# 11_SCREEN.net
KiCad netlist of a schematic drawn in Altium Designer
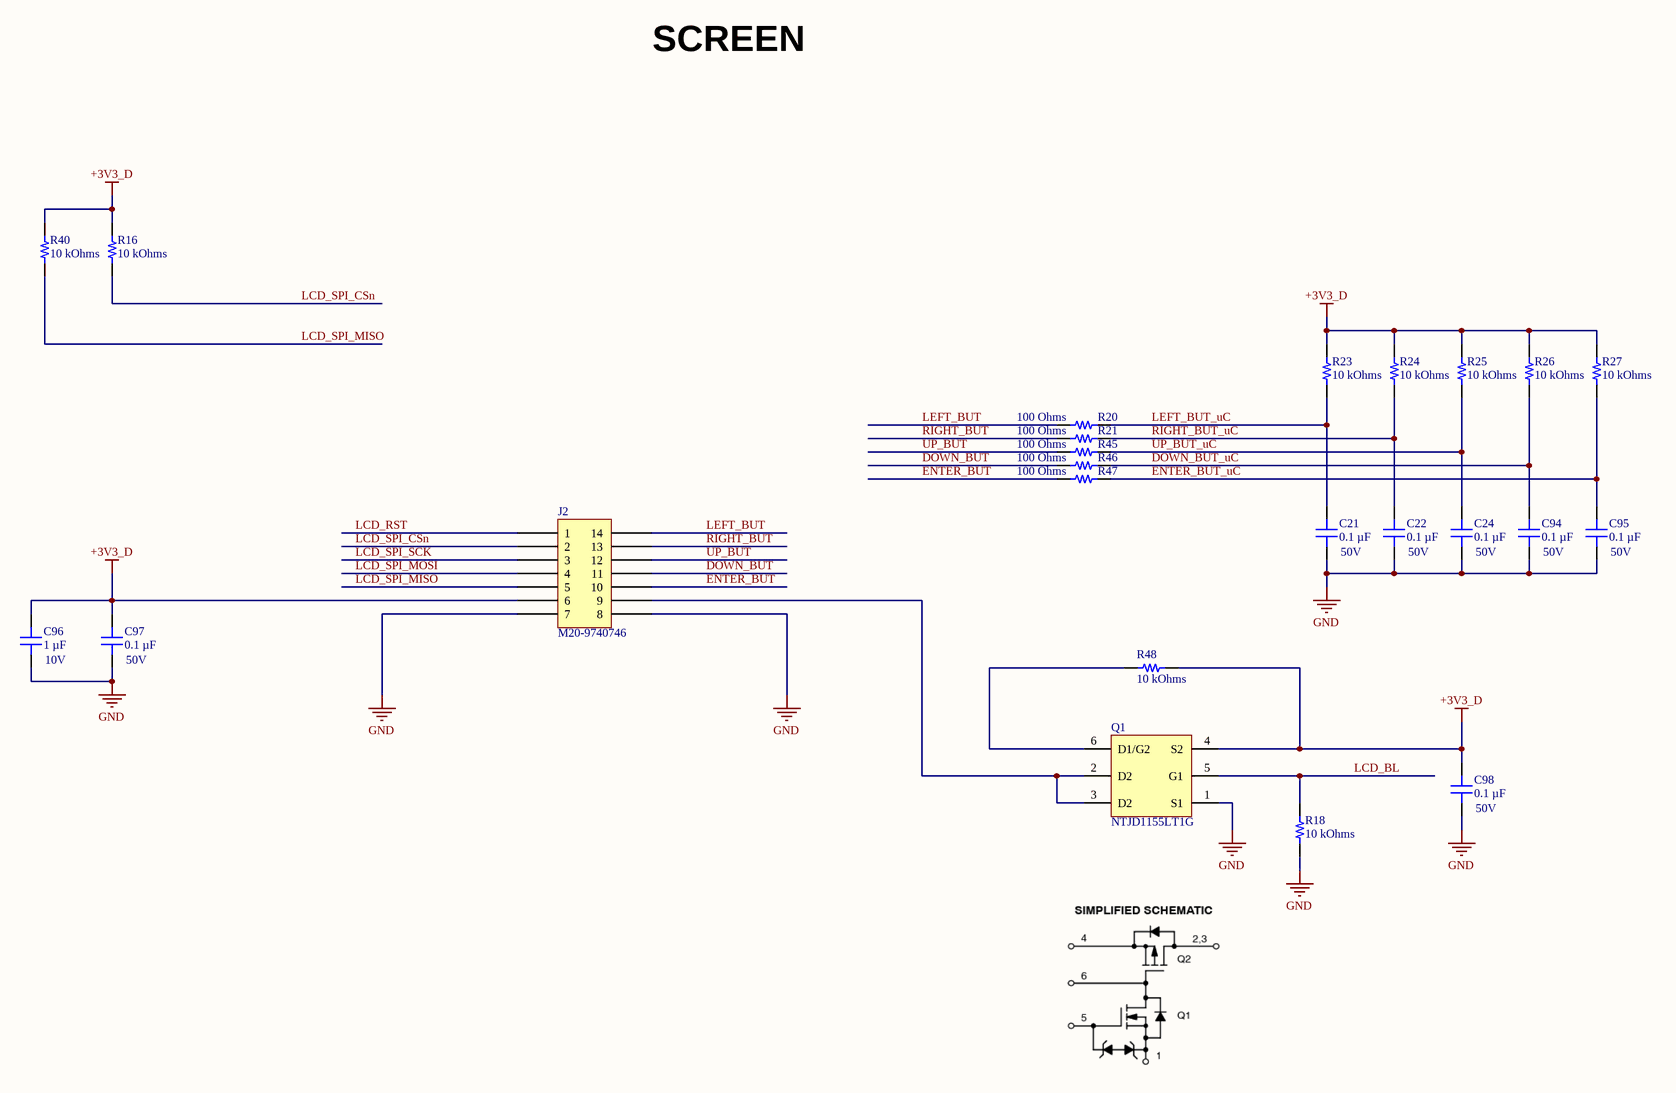
[diagram p0: 11_SCREEN.SchDoc]

(export (version "E")
  (design (tool "Eeschema 10.0.6"))
  (components
    (comp (ref "C21")
      (value "0.1 µF")
      (footprint "CAP 0402_1005")
      (description "CAP CER 0.1UF 50V X7R 0402")
      (fields
        (field (name "PART NUMBER") "GCM155R71H104KE02J")
        (field (name "CAPACITANCE") "0.1 µF")
        (field (name "MANUFACTURER") "Murata Electronics")
        (field (name "VOLTAGE - RATED") "50V")
      )
      (libsource (lib "Celestial Altium Library - altium_library") (part "Capacitor"))
    )
    (comp (ref "C22")
      (value "0.1 µF")
      (footprint "CAP 0402_1005")
      (description "CAP CER 0.1UF 50V X7R 0402")
      (fields
        (field (name "PART NUMBER") "GCM155R71H104KE02J")
        (field (name "CAPACITANCE") "0.1 µF")
        (field (name "MANUFACTURER") "Murata Electronics")
        (field (name "VOLTAGE - RATED") "50V")
      )
      (libsource (lib "Celestial Altium Library - altium_library") (part "Capacitor"))
    )
    (comp (ref "C24")
      (value "0.1 µF")
      (footprint "CAP 0402_1005")
      (description "CAP CER 0.1UF 50V X7R 0402")
      (fields
        (field (name "PART NUMBER") "GCM155R71H104KE02J")
        (field (name "CAPACITANCE") "0.1 µF")
        (field (name "MANUFACTURER") "Murata Electronics")
        (field (name "VOLTAGE - RATED") "50V")
      )
      (libsource (lib "Celestial Altium Library - altium_library") (part "Capacitor"))
    )
    (comp (ref "C94")
      (value "0.1 µF")
      (footprint "CAP 0402_1005")
      (description "CAP CER 0.1UF 50V X7R 0402")
      (fields
        (field (name "PART NUMBER") "GCM155R71H104KE02J")
        (field (name "CAPACITANCE") "0.1 µF")
        (field (name "MANUFACTURER") "Murata Electronics")
        (field (name "VOLTAGE - RATED") "50V")
      )
      (libsource (lib "Celestial Altium Library - altium_library") (part "Capacitor"))
    )
    (comp (ref "C95")
      (value "0.1 µF")
      (footprint "CAP 0402_1005")
      (description "CAP CER 0.1UF 50V X7R 0402")
      (fields
        (field (name "PART NUMBER") "GCM155R71H104KE02J")
        (field (name "CAPACITANCE") "0.1 µF")
        (field (name "MANUFACTURER") "Murata Electronics")
        (field (name "VOLTAGE - RATED") "50V")
      )
      (libsource (lib "Celestial Altium Library - altium_library") (part "Capacitor"))
    )
    (comp (ref "C96")
      (value "1 µF")
      (footprint "CAP 0402_1005")
      (description "CAP CER 1UF 10V X7S 0402")
      (fields
        (field (name "PART NUMBER") "GRM155C71A105KE11D")
        (field (name "CAPACITANCE") "1 µF")
        (field (name "MANUFACTURER") "Murata Electronics")
        (field (name "VOLTAGE - RATED") "10V")
      )
      (libsource (lib "Celestial Altium Library - altium_library") (part "Capacitor"))
    )
    (comp (ref "C97")
      (value "0.1 µF")
      (footprint "CAP 0402_1005")
      (description "CAP CER 0.1UF 50V X7R 0402")
      (fields
        (field (name "PART NUMBER") "GCM155R71H104KE02J")
        (field (name "CAPACITANCE") "0.1 µF")
        (field (name "MANUFACTURER") "Murata Electronics")
        (field (name "VOLTAGE - RATED") "50V")
      )
      (libsource (lib "Celestial Altium Library - altium_library") (part "Capacitor"))
    )
    (comp (ref "C98")
      (value "0.1 µF")
      (footprint "CAP 0402_1005")
      (description "CAP CER 0.1UF 50V X7R 0402")
      (fields
        (field (name "PART NUMBER") "GCM155R71H104KE02J")
        (field (name "CAPACITANCE") "0.1 µF")
        (field (name "MANUFACTURER") "Murata Electronics")
        (field (name "VOLTAGE - RATED") "50V")
      )
      (libsource (lib "Celestial Altium Library - altium_library") (part "Capacitor"))
    )
    (comp (ref "J2")
      (value "M20-9740746")
      (footprint "HARWIN M20-9740745")
      (description "CONN HEADER R/A 14POS 2.54MM")
      (fields (field (name "MANUFACTURER") "Harwin Inc."))
      (libsource (lib "Celestial Altium Library - altium_library") (part "2X7 PIN DU"))
    )
    (comp (ref "Q1")
      (value "NTJD1155LT1G")
      (footprint "ONSC-SC70-6-419B-02_W_V")
      (fields (field (name "MANUFACTURER") "On Semiconductor"))
      (libsource (lib "Altium Content Vault") (part "ONSC-PNMOS-6_D"))
    )
    (comp (ref "R16")
      (value "10 kOhms")
      (footprint "RES 0402_1005")
      (description "RES 10K OHM 1% 1/16W 0402")
      (fields (field (name "PART NUMBER") "RC0402FR-0710KL") (field (name "MANUFACTURER") "Yageo"))
      (libsource (lib "Celestial Altium Library - altium_library") (part "Resistor"))
    )
    (comp (ref "R18")
      (value "10 kOhms")
      (footprint "RES 0402_1005")
      (description "RES 10K OHM 1% 1/16W 0402")
      (fields (field (name "PART NUMBER") "RC0402FR-0710KL") (field (name "MANUFACTURER") "Yageo"))
      (libsource (lib "Celestial Altium Library - altium_library") (part "Resistor"))
    )
    (comp (ref "R20")
      (value "100 Ohms")
      (footprint "RES 0402_1005")
      (description "RES SMD 100 OHM 1% 1/16W 0402")
      (fields (field (name "PART NUMBER") "RT0402FRE07100RL") (field (name "MANUFACTURER") "Yageo"))
      (libsource (lib "Celestial Altium Library - altium_library") (part "Resistor"))
    )
    (comp (ref "R21")
      (value "100 Ohms")
      (footprint "RES 0402_1005")
      (description "RES SMD 100 OHM 1% 1/16W 0402")
      (fields (field (name "PART NUMBER") "RT0402FRE07100RL") (field (name "MANUFACTURER") "Yageo"))
      (libsource (lib "Celestial Altium Library - altium_library") (part "Resistor"))
    )
    (comp (ref "R23")
      (value "10 kOhms")
      (footprint "RES 0402_1005")
      (description "RES 10K OHM 1% 1/16W 0402")
      (fields (field (name "PART NUMBER") "RC0402FR-0710KL") (field (name "MANUFACTURER") "Yageo"))
      (libsource (lib "Celestial Altium Library - altium_library") (part "Resistor"))
    )
    (comp (ref "R24")
      (value "10 kOhms")
      (footprint "RES 0402_1005")
      (description "RES 10K OHM 1% 1/16W 0402")
      (fields (field (name "PART NUMBER") "RC0402FR-0710KL") (field (name "MANUFACTURER") "Yageo"))
      (libsource (lib "Celestial Altium Library - altium_library") (part "Resistor"))
    )
    (comp (ref "R25")
      (value "10 kOhms")
      (footprint "RES 0402_1005")
      (description "RES 10K OHM 1% 1/16W 0402")
      (fields (field (name "PART NUMBER") "RC0402FR-0710KL") (field (name "MANUFACTURER") "Yageo"))
      (libsource (lib "Celestial Altium Library - altium_library") (part "Resistor"))
    )
    (comp (ref "R26")
      (value "10 kOhms")
      (footprint "RES 0402_1005")
      (description "RES 10K OHM 1% 1/16W 0402")
      (fields (field (name "PART NUMBER") "RC0402FR-0710KL") (field (name "MANUFACTURER") "Yageo"))
      (libsource (lib "Celestial Altium Library - altium_library") (part "Resistor"))
    )
    (comp (ref "R27")
      (value "10 kOhms")
      (footprint "RES 0402_1005")
      (description "RES 10K OHM 1% 1/16W 0402")
      (fields (field (name "PART NUMBER") "RC0402FR-0710KL") (field (name "MANUFACTURER") "Yageo"))
      (libsource (lib "Celestial Altium Library - altium_library") (part "Resistor"))
    )
    (comp (ref "R40")
      (value "10 kOhms")
      (footprint "RES 0402_1005")
      (description "RES 10K OHM 1% 1/16W 0402")
      (fields (field (name "PART NUMBER") "RC0402FR-0710KL") (field (name "MANUFACTURER") "Yageo"))
      (libsource (lib "Celestial Altium Library - altium_library") (part "Resistor"))
    )
    (comp (ref "R45")
      (value "100 Ohms")
      (footprint "RES 0402_1005")
      (description "RES SMD 100 OHM 1% 1/16W 0402")
      (fields (field (name "PART NUMBER") "RT0402FRE07100RL") (field (name "MANUFACTURER") "Yageo"))
      (libsource (lib "Celestial Altium Library - altium_library") (part "Resistor"))
    )
    (comp (ref "R46")
      (value "100 Ohms")
      (footprint "RES 0402_1005")
      (description "RES SMD 100 OHM 1% 1/16W 0402")
      (fields (field (name "PART NUMBER") "RT0402FRE07100RL") (field (name "MANUFACTURER") "Yageo"))
      (libsource (lib "Celestial Altium Library - altium_library") (part "Resistor"))
    )
    (comp (ref "R47")
      (value "100 Ohms")
      (footprint "RES 0402_1005")
      (description "RES SMD 100 OHM 1% 1/16W 0402")
      (fields (field (name "PART NUMBER") "RT0402FRE07100RL") (field (name "MANUFACTURER") "Yageo"))
      (libsource (lib "Celestial Altium Library - altium_library") (part "Resistor"))
    )
    (comp (ref "R48")
      (value "10 kOhms")
      (footprint "RES 0402_1005")
      (description "RES 10K OHM 1% 1/16W 0402")
      (fields (field (name "PART NUMBER") "RC0402FR-0710KL") (field (name "MANUFACTURER") "Yageo"))
      (libsource (lib "Celestial Altium Library - altium_library") (part "Resistor"))
    )
  )
  (nets
    (net (code "1") (name "+3V3_D") (class "Default")
      (node (ref "C96") (pin "1") (pinfunction "1_1") (pintype "passive"))
      (node (ref "C97") (pin "2") (pinfunction "2_2") (pintype "passive"))
      (node (ref "C98") (pin "2") (pinfunction "2_2") (pintype "passive"))
      (node (ref "J2") (pin "6") (pinfunction "6_6") (pintype "passive"))
      (node (ref "Q1") (pin "4") (pinfunction "S2_4") (pintype "passive"))
      (node (ref "R16") (pin "2") (pinfunction "2_2") (pintype "passive"))
      (node (ref "R23") (pin "2") (pinfunction "2_2") (pintype "passive"))
      (node (ref "R24") (pin "2") (pinfunction "2_2") (pintype "passive"))
      (node (ref "R25") (pin "2") (pinfunction "2_2") (pintype "passive"))
      (node (ref "R26") (pin "2") (pinfunction "2_2") (pintype "passive"))
      (node (ref "R27") (pin "2") (pinfunction "2_2") (pintype "passive"))
      (node (ref "R40") (pin "2") (pinfunction "2_2") (pintype "passive"))
      (node (ref "R48") (pin "1") (pinfunction "1_1") (pintype "passive"))
    )
    (net (code "2") (name "/DOWN_BUT") (class "Default")
      (node (ref "J2") (pin "11") (pinfunction "11_11") (pintype "passive"))
      (node (ref "R46") (pin "1") (pinfunction "1_1") (pintype "passive"))
    )
    (net (code "3") (name "/DOWN_BUT_uC") (class "Default")
      (node (ref "C94") (pin "2") (pinfunction "2_2") (pintype "passive"))
      (node (ref "R26") (pin "1") (pinfunction "1_1") (pintype "passive"))
      (node (ref "R46") (pin "2") (pinfunction "2_2") (pintype "passive"))
    )
    (net (code "4") (name "/ENTER_BUT") (class "Default")
      (node (ref "J2") (pin "10") (pinfunction "10_10") (pintype "passive"))
      (node (ref "R47") (pin "1") (pinfunction "1_1") (pintype "passive"))
    )
    (net (code "5") (name "/ENTER_BUT_uC") (class "Default")
      (node (ref "C95") (pin "2") (pinfunction "2_2") (pintype "passive"))
      (node (ref "R27") (pin "1") (pinfunction "1_1") (pintype "passive"))
      (node (ref "R47") (pin "2") (pinfunction "2_2") (pintype "passive"))
    )
    (net (code "6") (name "/LCD_BL") (class "Default")
      (node (ref "Q1") (pin "5") (pinfunction "G1_5") (pintype "passive"))
      (node (ref "R18") (pin "2") (pinfunction "2_2") (pintype "passive"))
    )
    (net (code "7") (name "/LCD_RST") (class "Default")
      (node (ref "J2") (pin "1") (pinfunction "1_1") (pintype "passive"))
    )
    (net (code "8") (name "/LCD_SPI_CSn") (class "Default")
      (node (ref "J2") (pin "2") (pinfunction "2_2") (pintype "passive"))
      (node (ref "R16") (pin "1") (pinfunction "1_1") (pintype "passive"))
    )
    (net (code "9") (name "/LCD_SPI_MISO") (class "Default")
      (node (ref "J2") (pin "5") (pinfunction "5_5") (pintype "passive"))
      (node (ref "R40") (pin "1") (pinfunction "1_1") (pintype "passive"))
    )
    (net (code "10") (name "/LCD_SPI_MOSI") (class "Default")
      (node (ref "J2") (pin "4") (pinfunction "4_4") (pintype "passive"))
    )
    (net (code "11") (name "/LCD_SPI_SCK") (class "Default")
      (node (ref "J2") (pin "3") (pinfunction "3_3") (pintype "passive"))
    )
    (net (code "12") (name "/LEFT_BUT") (class "Default")
      (node (ref "J2") (pin "14") (pinfunction "14_14") (pintype "passive"))
      (node (ref "R20") (pin "1") (pinfunction "1_1") (pintype "passive"))
    )
    (net (code "13") (name "/LEFT_BUT_uC") (class "Default")
      (node (ref "C21") (pin "2") (pinfunction "2_2") (pintype "passive"))
      (node (ref "R20") (pin "2") (pinfunction "2_2") (pintype "passive"))
      (node (ref "R23") (pin "1") (pinfunction "1_1") (pintype "passive"))
    )
    (net (code "14") (name "/RIGHT_BUT") (class "Default")
      (node (ref "J2") (pin "13") (pinfunction "13_13") (pintype "passive"))
      (node (ref "R21") (pin "1") (pinfunction "1_1") (pintype "passive"))
    )
    (net (code "15") (name "/RIGHT_BUT_uC") (class "Default")
      (node (ref "C22") (pin "2") (pinfunction "2_2") (pintype "passive"))
      (node (ref "R21") (pin "2") (pinfunction "2_2") (pintype "passive"))
      (node (ref "R24") (pin "1") (pinfunction "1_1") (pintype "passive"))
    )
    (net (code "16") (name "/UP_BUT") (class "Default")
      (node (ref "J2") (pin "12") (pinfunction "12_12") (pintype "passive"))
      (node (ref "R45") (pin "1") (pinfunction "1_1") (pintype "passive"))
    )
    (net (code "17") (name "/UP_BUT_uC") (class "Default")
      (node (ref "C24") (pin "2") (pinfunction "2_2") (pintype "passive"))
      (node (ref "R25") (pin "1") (pinfunction "1_1") (pintype "passive"))
      (node (ref "R45") (pin "2") (pinfunction "2_2") (pintype "passive"))
    )
    (net (code "18") (name "GND") (class "Default")
      (node (ref "C21") (pin "1") (pinfunction "1_1") (pintype "passive"))
      (node (ref "C22") (pin "1") (pinfunction "1_1") (pintype "passive"))
      (node (ref "C24") (pin "1") (pinfunction "1_1") (pintype "passive"))
      (node (ref "C94") (pin "1") (pinfunction "1_1") (pintype "passive"))
      (node (ref "C95") (pin "1") (pinfunction "1_1") (pintype "passive"))
      (node (ref "C96") (pin "2") (pinfunction "2_2") (pintype "passive"))
      (node (ref "C97") (pin "1") (pinfunction "1_1") (pintype "passive"))
      (node (ref "C98") (pin "1") (pinfunction "1_1") (pintype "passive"))
      (node (ref "J2") (pin "7") (pinfunction "7_7") (pintype "passive"))
      (node (ref "J2") (pin "8") (pinfunction "8_8") (pintype "passive"))
      (node (ref "Q1") (pin "1") (pinfunction "S1_1") (pintype "passive"))
      (node (ref "R18") (pin "1") (pinfunction "1_1") (pintype "passive"))
    )
    (net (code "19") (name "Net-(J2-Pad9)") (class "Default")
      (node (ref "J2") (pin "9") (pinfunction "9_9") (pintype "passive"))
      (node (ref "Q1") (pin "2") (pinfunction "D2_2") (pintype "passive"))
      (node (ref "Q1") (pin "3") (pinfunction "D2_3") (pintype "passive"))
    )
    (net (code "20") (name "Net-(Q1-D1{slash}G2)") (class "Default")
      (node (ref "Q1") (pin "6") (pinfunction "D1/G2_6") (pintype "passive"))
      (node (ref "R48") (pin "2") (pinfunction "2_2") (pintype "passive"))
    )
  )
)
